# controll_8motor_dac.net
KiCad netlist of a schematic drawn in EAGLE
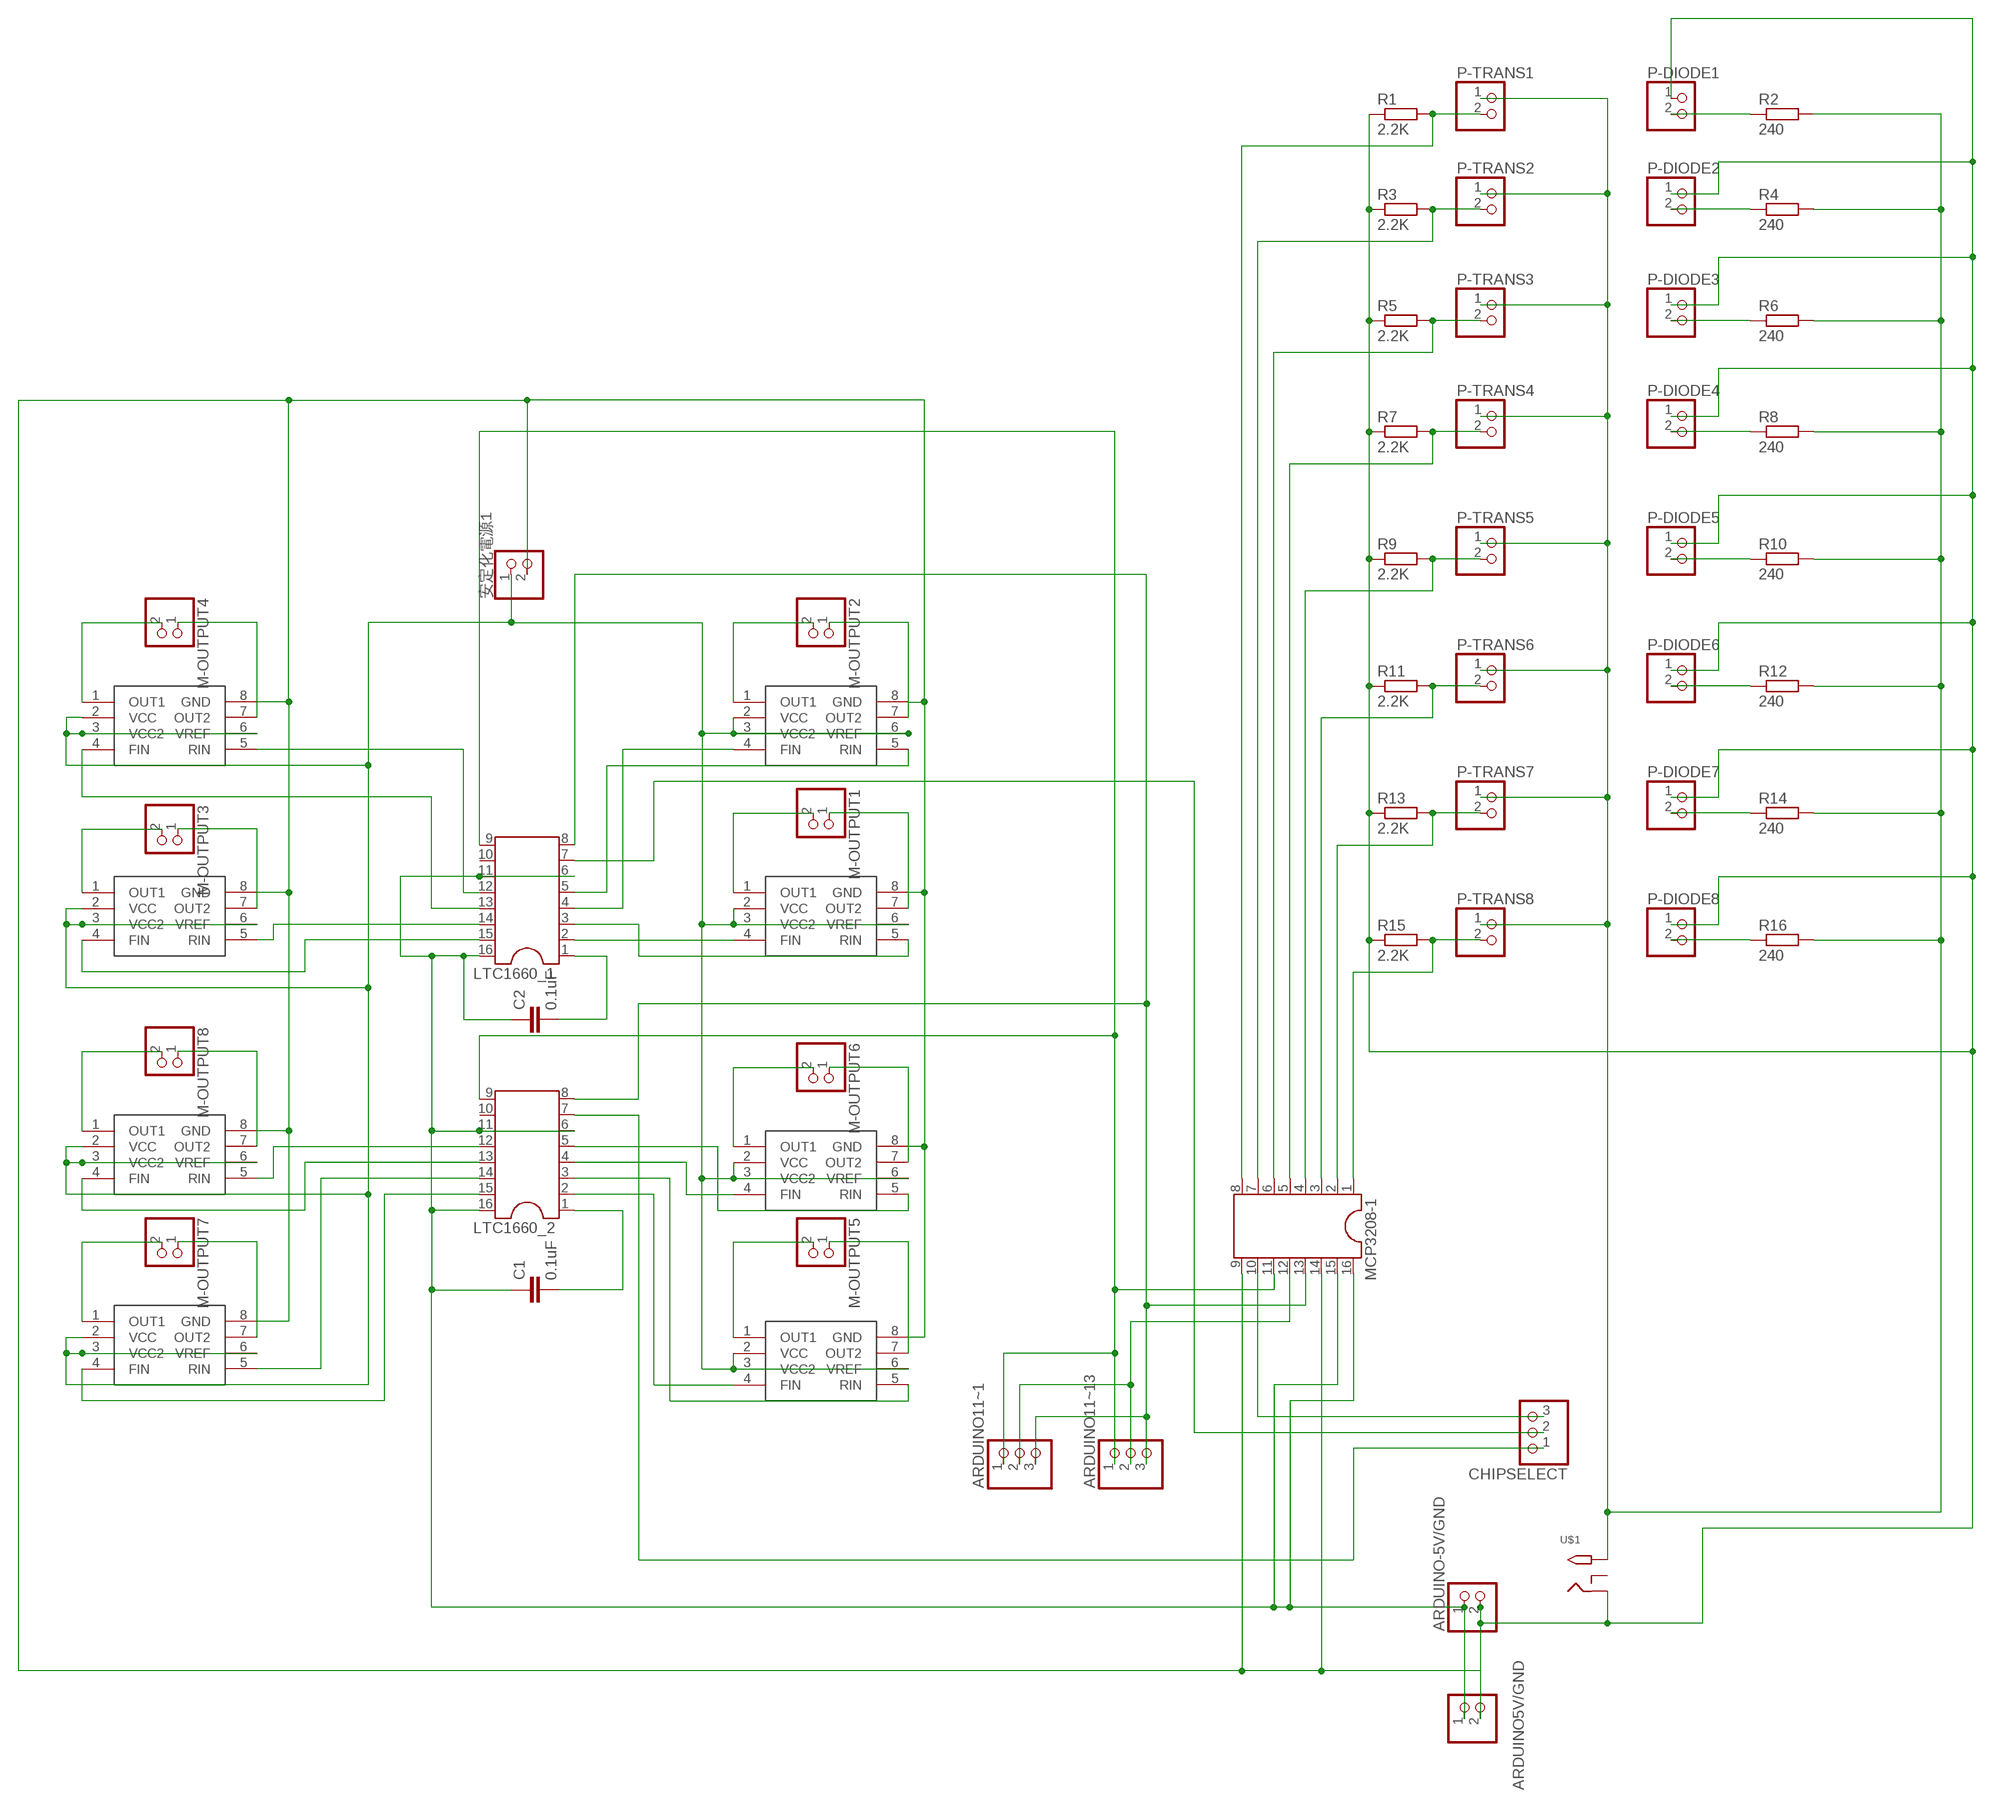
[diagram p0: schematic, sheet 1]

(export (version "E")
  (design (tool "Eeschema 10.0.6"))
  (components
    (comp (ref "ARDUINO-5V/GND")
      (value "PINHD-1X2")
      (footprint "eagle-import:1X02")
      (libsource (lib "eagle-import") (part "PINHD-1X2"))
    )
    (comp (ref "ARDUINO5V/GND")
      (value "PINHD-1X2")
      (footprint "eagle-import:1X02")
      (libsource (lib "eagle-import") (part "PINHD-1X2"))
    )
    (comp (ref "ARDUINO11~1")
      (value "PINHD-1X3")
      (footprint "eagle-import:1X03")
      (libsource (lib "eagle-import") (part "PINHD-1X3"))
    )
    (comp (ref "ARDUINO11~13")
      (value "PINHD-1X3")
      (footprint "eagle-import:1X03")
      (libsource (lib "eagle-import") (part "PINHD-1X3"))
    )
    (comp (ref "C1")
      (value "0.1uF")
      (footprint "eagle-import:C025-024X044")
      (libsource (lib "eagle-import") (part "C-EU025-024X044"))
    )
    (comp (ref "C2")
      (value "0.1uF")
      (footprint "eagle-import:C025-024X044")
      (libsource (lib "eagle-import") (part "C-EU025-024X044"))
    )
    (comp (ref "CHIPSELECT")
      (value "PINHD-1X3")
      (footprint "eagle-import:1X03")
      (libsource (lib "eagle-import") (part "PINHD-1X3"))
    )
    (comp (ref "LTC1660_1")
      (value "DIL16S")
      (footprint "eagle-import:SOCKET-16")
      (libsource (lib "eagle-import") (part "DIL16S"))
    )
    (comp (ref "LTC1660_2")
      (value "DIL16S")
      (footprint "eagle-import:SOCKET-16")
      (libsource (lib "eagle-import") (part "DIL16S"))
    )
    (comp (ref "M-DRIVER_1")
      (value "BD6211F-E2")
      (footprint "eagle-import:BD6211F-E2")
      (libsource (lib "eagle-import") (part "BD6211F-E2"))
    )
    (comp (ref "M-DRIVER_2")
      (value "BD6211F-E2")
      (footprint "eagle-import:BD6211F-E2")
      (libsource (lib "eagle-import") (part "BD6211F-E2"))
    )
    (comp (ref "M-DRIVER_3")
      (value "BD6211F-E2")
      (footprint "eagle-import:BD6211F-E2")
      (libsource (lib "eagle-import") (part "BD6211F-E2"))
    )
    (comp (ref "M-DRIVER_4")
      (value "BD6211F-E2")
      (footprint "eagle-import:BD6211F-E2")
      (libsource (lib "eagle-import") (part "BD6211F-E2"))
    )
    (comp (ref "M-DRIVER_5")
      (value "BD6211F-E2")
      (footprint "eagle-import:BD6211F-E2")
      (libsource (lib "eagle-import") (part "BD6211F-E2"))
    )
    (comp (ref "M-DRIVER_6")
      (value "BD6211F-E2")
      (footprint "eagle-import:BD6211F-E2")
      (libsource (lib "eagle-import") (part "BD6211F-E2"))
    )
    (comp (ref "M-DRIVER_7")
      (value "BD6211F-E2")
      (footprint "eagle-import:BD6211F-E2")
      (libsource (lib "eagle-import") (part "BD6211F-E2"))
    )
    (comp (ref "M-DRIVER_8")
      (value "BD6211F-E2")
      (footprint "eagle-import:BD6211F-E2")
      (libsource (lib "eagle-import") (part "BD6211F-E2"))
    )
    (comp (ref "M-OUTPUT1")
      (value "PINHD-1X2")
      (footprint "eagle-import:1X02")
      (libsource (lib "eagle-import") (part "PINHD-1X2"))
    )
    (comp (ref "M-OUTPUT2")
      (value "PINHD-1X2")
      (footprint "eagle-import:1X02")
      (libsource (lib "eagle-import") (part "PINHD-1X2"))
    )
    (comp (ref "M-OUTPUT3")
      (value "PINHD-1X2")
      (footprint "eagle-import:1X02")
      (libsource (lib "eagle-import") (part "PINHD-1X2"))
    )
    (comp (ref "M-OUTPUT4")
      (value "PINHD-1X2")
      (footprint "eagle-import:1X02")
      (libsource (lib "eagle-import") (part "PINHD-1X2"))
    )
    (comp (ref "M-OUTPUT5")
      (value "PINHD-1X2")
      (footprint "eagle-import:1X02")
      (libsource (lib "eagle-import") (part "PINHD-1X2"))
    )
    (comp (ref "M-OUTPUT6")
      (value "PINHD-1X2")
      (footprint "eagle-import:1X02")
      (libsource (lib "eagle-import") (part "PINHD-1X2"))
    )
    (comp (ref "M-OUTPUT7")
      (value "PINHD-1X2")
      (footprint "eagle-import:1X02")
      (libsource (lib "eagle-import") (part "PINHD-1X2"))
    )
    (comp (ref "M-OUTPUT8")
      (value "PINHD-1X2")
      (footprint "eagle-import:1X02")
      (libsource (lib "eagle-import") (part "PINHD-1X2"))
    )
    (comp (ref "MCP3208‐1")
      (value "DIL16S")
      (footprint "eagle-import:SOCKET-16")
      (libsource (lib "eagle-import") (part "DIL16S"))
    )
    (comp (ref "P-DIODE1")
      (value "PINHD-1X2")
      (footprint "eagle-import:1X02")
      (libsource (lib "eagle-import") (part "PINHD-1X2"))
    )
    (comp (ref "P-DIODE2")
      (value "PINHD-1X2")
      (footprint "eagle-import:1X02")
      (libsource (lib "eagle-import") (part "PINHD-1X2"))
    )
    (comp (ref "P-DIODE3")
      (value "PINHD-1X2")
      (footprint "eagle-import:1X02")
      (libsource (lib "eagle-import") (part "PINHD-1X2"))
    )
    (comp (ref "P-DIODE4")
      (value "PINHD-1X2")
      (footprint "eagle-import:1X02")
      (libsource (lib "eagle-import") (part "PINHD-1X2"))
    )
    (comp (ref "P-DIODE5")
      (value "PINHD-1X2")
      (footprint "eagle-import:1X02")
      (libsource (lib "eagle-import") (part "PINHD-1X2"))
    )
    (comp (ref "P-DIODE6")
      (value "PINHD-1X2")
      (footprint "eagle-import:1X02")
      (libsource (lib "eagle-import") (part "PINHD-1X2"))
    )
    (comp (ref "P-DIODE7")
      (value "PINHD-1X2")
      (footprint "eagle-import:1X02")
      (libsource (lib "eagle-import") (part "PINHD-1X2"))
    )
    (comp (ref "P-DIODE8")
      (value "PINHD-1X2")
      (footprint "eagle-import:1X02")
      (libsource (lib "eagle-import") (part "PINHD-1X2"))
    )
    (comp (ref "P-TRANS1")
      (value "PINHD-1X2")
      (footprint "eagle-import:1X02")
      (libsource (lib "eagle-import") (part "PINHD-1X2"))
    )
    (comp (ref "P-TRANS2")
      (value "PINHD-1X2")
      (footprint "eagle-import:1X02")
      (libsource (lib "eagle-import") (part "PINHD-1X2"))
    )
    (comp (ref "P-TRANS3")
      (value "PINHD-1X2")
      (footprint "eagle-import:1X02")
      (libsource (lib "eagle-import") (part "PINHD-1X2"))
    )
    (comp (ref "P-TRANS4")
      (value "PINHD-1X2")
      (footprint "eagle-import:1X02")
      (libsource (lib "eagle-import") (part "PINHD-1X2"))
    )
    (comp (ref "P-TRANS5")
      (value "PINHD-1X2")
      (footprint "eagle-import:1X02")
      (libsource (lib "eagle-import") (part "PINHD-1X2"))
    )
    (comp (ref "P-TRANS6")
      (value "PINHD-1X2")
      (footprint "eagle-import:1X02")
      (libsource (lib "eagle-import") (part "PINHD-1X2"))
    )
    (comp (ref "P-TRANS7")
      (value "PINHD-1X2")
      (footprint "eagle-import:1X02")
      (libsource (lib "eagle-import") (part "PINHD-1X2"))
    )
    (comp (ref "P-TRANS8")
      (value "PINHD-1X2")
      (footprint "eagle-import:1X02")
      (libsource (lib "eagle-import") (part "PINHD-1X2"))
    )
    (comp (ref "R1")
      (value "2.2K")
      (footprint "eagle-import:0204V")
      (libsource (lib "eagle-import") (part "R-EU_0204/2V"))
    )
    (comp (ref "R2")
      (value "240")
      (footprint "eagle-import:0204V")
      (libsource (lib "eagle-import") (part "R-EU_0204/2V"))
    )
    (comp (ref "R3")
      (value "2.2K")
      (footprint "eagle-import:0204V")
      (libsource (lib "eagle-import") (part "R-EU_0204/2V"))
    )
    (comp (ref "R4")
      (value "240")
      (footprint "eagle-import:0204V")
      (libsource (lib "eagle-import") (part "R-EU_0204/2V"))
    )
    (comp (ref "R5")
      (value "2.2K")
      (footprint "eagle-import:0204V")
      (libsource (lib "eagle-import") (part "R-EU_0204/2V"))
    )
    (comp (ref "R6")
      (value "240")
      (footprint "eagle-import:0204V")
      (libsource (lib "eagle-import") (part "R-EU_0204/2V"))
    )
    (comp (ref "R7")
      (value "2.2K")
      (footprint "eagle-import:0204V")
      (libsource (lib "eagle-import") (part "R-EU_0204/2V"))
    )
    (comp (ref "R8")
      (value "240")
      (footprint "eagle-import:0204V")
      (libsource (lib "eagle-import") (part "R-EU_0204/2V"))
    )
    (comp (ref "R9")
      (value "2.2K")
      (footprint "eagle-import:0204V")
      (libsource (lib "eagle-import") (part "R-EU_0204/2V"))
    )
    (comp (ref "R10")
      (value "240")
      (footprint "eagle-import:0204V")
      (libsource (lib "eagle-import") (part "R-EU_0204/2V"))
    )
    (comp (ref "R11")
      (value "2.2K")
      (footprint "eagle-import:0204V")
      (libsource (lib "eagle-import") (part "R-EU_0204/2V"))
    )
    (comp (ref "R12")
      (value "240")
      (footprint "eagle-import:0204V")
      (libsource (lib "eagle-import") (part "R-EU_0204/2V"))
    )
    (comp (ref "R13")
      (value "2.2K")
      (footprint "eagle-import:0204V")
      (libsource (lib "eagle-import") (part "R-EU_0204/2V"))
    )
    (comp (ref "R14")
      (value "240")
      (footprint "eagle-import:0204V")
      (libsource (lib "eagle-import") (part "R-EU_0204/2V"))
    )
    (comp (ref "R15")
      (value "2.2K")
      (footprint "eagle-import:0204V")
      (libsource (lib "eagle-import") (part "R-EU_0204/2V"))
    )
    (comp (ref "R16")
      (value "240")
      (footprint "eagle-import:0204V")
      (libsource (lib "eagle-import") (part "R-EU_0204/2V"))
    )
    (comp (ref "U$1")
      (value "2.1MMJACKTHM")
      (footprint "eagle-import:PJ-102A")
      (libsource (lib "eagle-import") (part "2.1MMJACKTHM"))
    )
    (comp (ref "安定化電源1")
      (value "PINHD-1X2")
      (footprint "eagle-import:1X02")
      (libsource (lib "eagle-import") (part "PINHD-1X2"))
    )
  )
  (nets
    (net (code "1") (name "Net-(ARDUINO-5V/GND-Pad1)") (class "Default")
      (node (ref "ARDUINO-5V/GND") (pin "1") (pinfunction "1_1") (pintype "passive"))
      (node (ref "ARDUINO5V/GND") (pin "1") (pinfunction "1_1") (pintype "passive"))
      (node (ref "C1") (pin "1") (pinfunction "1_1") (pintype "passive"))
      (node (ref "C2") (pin "1") (pinfunction "1_1") (pintype "passive"))
      (node (ref "LTC1660_1") (pin "11") (pinfunction "11_11") (pintype "passive"))
      (node (ref "LTC1660_1") (pin "16") (pinfunction "16_16") (pintype "passive"))
      (node (ref "LTC1660_1") (pin "6") (pinfunction "6_6") (pintype "passive"))
      (node (ref "LTC1660_2") (pin "11") (pinfunction "11_11") (pintype "passive"))
      (node (ref "LTC1660_2") (pin "16") (pinfunction "16_16") (pintype "passive"))
      (node (ref "LTC1660_2") (pin "6") (pinfunction "6_6") (pintype "passive"))
      (node (ref "MCP3208‐1") (pin "15") (pinfunction "15_15") (pintype "passive"))
      (node (ref "MCP3208‐1") (pin "16") (pinfunction "16_16") (pintype "passive"))
    )
    (net (code "2") (name "Net-(ARDUINO11~1-Pad1)") (class "Default")
      (node (ref "ARDUINO11~1") (pin "1") (pinfunction "1_1") (pintype "passive"))
      (node (ref "ARDUINO11~13") (pin "1") (pinfunction "1_1") (pintype "passive"))
      (node (ref "LTC1660_1") (pin "9") (pinfunction "9_9") (pintype "passive"))
      (node (ref "LTC1660_2") (pin "9") (pinfunction "9_9") (pintype "passive"))
      (node (ref "MCP3208‐1") (pin "11") (pinfunction "11_11") (pintype "passive"))
    )
    (net (code "3") (name "Net-(ARDUINO11~1-Pad2)") (class "Default")
      (node (ref "ARDUINO11~1") (pin "2") (pinfunction "2_2") (pintype "passive"))
      (node (ref "ARDUINO11~13") (pin "2") (pinfunction "2_2") (pintype "passive"))
      (node (ref "MCP3208‐1") (pin "12") (pinfunction "12_12") (pintype "passive"))
    )
    (net (code "4") (name "Net-(ARDUINO11~1-Pad3)") (class "Default")
      (node (ref "ARDUINO11~1") (pin "3") (pinfunction "3_3") (pintype "passive"))
      (node (ref "ARDUINO11~13") (pin "3") (pinfunction "3_3") (pintype "passive"))
      (node (ref "LTC1660_1") (pin "8") (pinfunction "8_8") (pintype "passive"))
      (node (ref "LTC1660_2") (pin "8") (pinfunction "8_8") (pintype "passive"))
      (node (ref "MCP3208‐1") (pin "13") (pinfunction "13_13") (pintype "passive"))
    )
    (net (code "5") (name "Net-(C1-Pad2)") (class "Default")
      (node (ref "C1") (pin "2") (pinfunction "2_2") (pintype "passive"))
      (node (ref "LTC1660_2") (pin "1") (pinfunction "1_1") (pintype "passive"))
    )
    (net (code "6") (name "Net-(C2-Pad2)") (class "Default")
      (node (ref "C2") (pin "2") (pinfunction "2_2") (pintype "passive"))
      (node (ref "LTC1660_1") (pin "1") (pinfunction "1_1") (pintype "passive"))
    )
    (net (code "7") (name "Net-(CHIPSELECT-Pad1)") (class "Default")
      (node (ref "CHIPSELECT") (pin "1") (pinfunction "1_1") (pintype "passive"))
      (node (ref "LTC1660_2") (pin "7") (pinfunction "7_7") (pintype "passive"))
    )
    (net (code "8") (name "Net-(CHIPSELECT-Pad2)") (class "Default")
      (node (ref "CHIPSELECT") (pin "2") (pinfunction "2_2") (pintype "passive"))
      (node (ref "LTC1660_1") (pin "7") (pinfunction "7_7") (pintype "passive"))
    )
    (net (code "9") (name "Net-(CHIPSELECT-Pad3)") (class "Default")
      (node (ref "CHIPSELECT") (pin "3") (pinfunction "3_3") (pintype "passive"))
      (node (ref "MCP3208‐1") (pin "10") (pinfunction "10_10") (pintype "passive"))
    )
    (net (code "10") (name "Net-(M-DRIVER_1-FIN)") (class "Default")
      (node (ref "LTC1660_1") (pin "2") (pinfunction "2_2") (pintype "passive"))
      (node (ref "M-DRIVER_1") (pin "4") (pinfunction "FIN_4") (pintype "bidirectional"))
    )
    (net (code "11") (name "Net-(M-DRIVER_1-GND)") (class "Default")
      (node (ref "ARDUINO-5V/GND") (pin "2") (pinfunction "2_2") (pintype "passive"))
      (node (ref "ARDUINO5V/GND") (pin "2") (pinfunction "2_2") (pintype "passive"))
      (node (ref "M-DRIVER_1") (pin "8") (pinfunction "GND_8") (pintype "bidirectional"))
      (node (ref "M-DRIVER_2") (pin "8") (pinfunction "GND_8") (pintype "bidirectional"))
      (node (ref "M-DRIVER_3") (pin "8") (pinfunction "GND_8") (pintype "bidirectional"))
      (node (ref "M-DRIVER_4") (pin "8") (pinfunction "GND_8") (pintype "bidirectional"))
      (node (ref "M-DRIVER_5") (pin "8") (pinfunction "GND_8") (pintype "bidirectional"))
      (node (ref "M-DRIVER_6") (pin "8") (pinfunction "GND_8") (pintype "bidirectional"))
      (node (ref "M-DRIVER_7") (pin "8") (pinfunction "GND_8") (pintype "bidirectional"))
      (node (ref "M-DRIVER_8") (pin "8") (pinfunction "GND_8") (pintype "bidirectional"))
      (node (ref "MCP3208‐1") (pin "14") (pinfunction "14_14") (pintype "passive"))
      (node (ref "MCP3208‐1") (pin "9") (pinfunction "9_9") (pintype "passive"))
      (node (ref "P-DIODE1") (pin "1") (pinfunction "1_1") (pintype "passive"))
      (node (ref "P-DIODE2") (pin "1") (pinfunction "1_1") (pintype "passive"))
      (node (ref "P-DIODE3") (pin "1") (pinfunction "1_1") (pintype "passive"))
      (node (ref "P-DIODE4") (pin "1") (pinfunction "1_1") (pintype "passive"))
      (node (ref "P-DIODE5") (pin "1") (pinfunction "1_1") (pintype "passive"))
      (node (ref "P-DIODE6") (pin "1") (pinfunction "1_1") (pintype "passive"))
      (node (ref "P-DIODE7") (pin "1") (pinfunction "1_1") (pintype "passive"))
      (node (ref "P-DIODE8") (pin "1") (pinfunction "1_1") (pintype "passive"))
      (node (ref "R1") (pin "1") (pinfunction "1_1") (pintype "passive"))
      (node (ref "R11") (pin "1") (pinfunction "1_1") (pintype "passive"))
      (node (ref "R13") (pin "1") (pinfunction "1_1") (pintype "passive"))
      (node (ref "R15") (pin "1") (pinfunction "1_1") (pintype "passive"))
      (node (ref "R3") (pin "1") (pinfunction "1_1") (pintype "passive"))
      (node (ref "R5") (pin "1") (pinfunction "1_1") (pintype "passive"))
      (node (ref "R7") (pin "1") (pinfunction "1_1") (pintype "passive"))
      (node (ref "R9") (pin "1") (pinfunction "1_1") (pintype "passive"))
      (node (ref "U$1") (pin "RING") (pinfunction "RING_RING") (pintype "bidirectional"))
      (node (ref "安定化電源1") (pin "2") (pinfunction "2_2") (pintype "passive"))
    )
    (net (code "12") (name "Net-(M-DRIVER_1-OUT1)") (class "Default")
      (node (ref "M-DRIVER_1") (pin "1") (pinfunction "OUT1_1") (pintype "bidirectional"))
      (node (ref "M-OUTPUT1") (pin "2") (pinfunction "2_2") (pintype "passive"))
    )
    (net (code "13") (name "Net-(M-DRIVER_1-OUT2)") (class "Default")
      (node (ref "M-DRIVER_1") (pin "7") (pinfunction "OUT2_7") (pintype "bidirectional"))
      (node (ref "M-OUTPUT1") (pin "1") (pinfunction "1_1") (pintype "passive"))
    )
    (net (code "14") (name "Net-(M-DRIVER_1-RIN)") (class "Default")
      (node (ref "LTC1660_1") (pin "3") (pinfunction "3_3") (pintype "passive"))
      (node (ref "M-DRIVER_1") (pin "5") (pinfunction "RIN_5") (pintype "bidirectional"))
    )
    (net (code "15") (name "Net-(M-DRIVER_1-VCC)") (class "Default")
      (node (ref "M-DRIVER_1") (pin "2") (pinfunction "VCC_2") (pintype "bidirectional"))
      (node (ref "M-DRIVER_1") (pin "3") (pinfunction "VCC2_3") (pintype "bidirectional"))
      (node (ref "M-DRIVER_1") (pin "6") (pinfunction "VREF_6") (pintype "bidirectional"))
      (node (ref "M-DRIVER_2") (pin "2") (pinfunction "VCC_2") (pintype "bidirectional"))
      (node (ref "M-DRIVER_2") (pin "3") (pinfunction "VCC2_3") (pintype "bidirectional"))
      (node (ref "M-DRIVER_2") (pin "6") (pinfunction "VREF_6") (pintype "bidirectional"))
      (node (ref "M-DRIVER_3") (pin "2") (pinfunction "VCC_2") (pintype "bidirectional"))
      (node (ref "M-DRIVER_3") (pin "3") (pinfunction "VCC2_3") (pintype "bidirectional"))
      (node (ref "M-DRIVER_3") (pin "6") (pinfunction "VREF_6") (pintype "bidirectional"))
      (node (ref "M-DRIVER_4") (pin "2") (pinfunction "VCC_2") (pintype "bidirectional"))
      (node (ref "M-DRIVER_4") (pin "3") (pinfunction "VCC2_3") (pintype "bidirectional"))
      (node (ref "M-DRIVER_4") (pin "6") (pinfunction "VREF_6") (pintype "bidirectional"))
      (node (ref "M-DRIVER_5") (pin "2") (pinfunction "VCC_2") (pintype "bidirectional"))
      (node (ref "M-DRIVER_5") (pin "3") (pinfunction "VCC2_3") (pintype "bidirectional"))
      (node (ref "M-DRIVER_5") (pin "6") (pinfunction "VREF_6") (pintype "bidirectional"))
      (node (ref "M-DRIVER_6") (pin "2") (pinfunction "VCC_2") (pintype "bidirectional"))
      (node (ref "M-DRIVER_6") (pin "3") (pinfunction "VCC2_3") (pintype "bidirectional"))
      (node (ref "M-DRIVER_6") (pin "6") (pinfunction "VREF_6") (pintype "bidirectional"))
      (node (ref "M-DRIVER_7") (pin "2") (pinfunction "VCC_2") (pintype "bidirectional"))
      (node (ref "M-DRIVER_7") (pin "3") (pinfunction "VCC2_3") (pintype "bidirectional"))
      (node (ref "M-DRIVER_7") (pin "6") (pinfunction "VREF_6") (pintype "bidirectional"))
      (node (ref "M-DRIVER_8") (pin "2") (pinfunction "VCC_2") (pintype "bidirectional"))
      (node (ref "M-DRIVER_8") (pin "3") (pinfunction "VCC2_3") (pintype "bidirectional"))
      (node (ref "M-DRIVER_8") (pin "6") (pinfunction "VREF_6") (pintype "bidirectional"))
      (node (ref "安定化電源1") (pin "1") (pinfunction "1_1") (pintype "passive"))
    )
    (net (code "16") (name "Net-(M-DRIVER_2-FIN)") (class "Default")
      (node (ref "LTC1660_1") (pin "4") (pinfunction "4_4") (pintype "passive"))
      (node (ref "M-DRIVER_2") (pin "4") (pinfunction "FIN_4") (pintype "bidirectional"))
    )
    (net (code "17") (name "Net-(M-DRIVER_2-OUT1)") (class "Default")
      (node (ref "M-DRIVER_2") (pin "1") (pinfunction "OUT1_1") (pintype "bidirectional"))
      (node (ref "M-OUTPUT2") (pin "2") (pinfunction "2_2") (pintype "passive"))
    )
    (net (code "18") (name "Net-(M-DRIVER_2-OUT2)") (class "Default")
      (node (ref "M-DRIVER_2") (pin "7") (pinfunction "OUT2_7") (pintype "bidirectional"))
      (node (ref "M-OUTPUT2") (pin "1") (pinfunction "1_1") (pintype "passive"))
    )
    (net (code "19") (name "Net-(M-DRIVER_2-RIN)") (class "Default")
      (node (ref "LTC1660_1") (pin "5") (pinfunction "5_5") (pintype "passive"))
      (node (ref "M-DRIVER_2") (pin "5") (pinfunction "RIN_5") (pintype "bidirectional"))
    )
    (net (code "20") (name "Net-(M-DRIVER_3-FIN)") (class "Default")
      (node (ref "LTC1660_1") (pin "15") (pinfunction "15_15") (pintype "passive"))
      (node (ref "M-DRIVER_3") (pin "4") (pinfunction "FIN_4") (pintype "bidirectional"))
    )
    (net (code "21") (name "Net-(M-DRIVER_3-OUT1)") (class "Default")
      (node (ref "M-DRIVER_3") (pin "1") (pinfunction "OUT1_1") (pintype "bidirectional"))
      (node (ref "M-OUTPUT3") (pin "2") (pinfunction "2_2") (pintype "passive"))
    )
    (net (code "22") (name "Net-(M-DRIVER_3-OUT2)") (class "Default")
      (node (ref "M-DRIVER_3") (pin "7") (pinfunction "OUT2_7") (pintype "bidirectional"))
      (node (ref "M-OUTPUT3") (pin "1") (pinfunction "1_1") (pintype "passive"))
    )
    (net (code "23") (name "Net-(M-DRIVER_3-RIN)") (class "Default")
      (node (ref "LTC1660_1") (pin "14") (pinfunction "14_14") (pintype "passive"))
      (node (ref "M-DRIVER_3") (pin "5") (pinfunction "RIN_5") (pintype "bidirectional"))
    )
    (net (code "24") (name "Net-(M-DRIVER_4-FIN)") (class "Default")
      (node (ref "LTC1660_1") (pin "13") (pinfunction "13_13") (pintype "passive"))
      (node (ref "M-DRIVER_4") (pin "4") (pinfunction "FIN_4") (pintype "bidirectional"))
    )
    (net (code "25") (name "Net-(M-DRIVER_4-OUT1)") (class "Default")
      (node (ref "M-DRIVER_4") (pin "1") (pinfunction "OUT1_1") (pintype "bidirectional"))
      (node (ref "M-OUTPUT4") (pin "2") (pinfunction "2_2") (pintype "passive"))
    )
    (net (code "26") (name "Net-(M-DRIVER_4-OUT2)") (class "Default")
      (node (ref "M-DRIVER_4") (pin "7") (pinfunction "OUT2_7") (pintype "bidirectional"))
      (node (ref "M-OUTPUT4") (pin "1") (pinfunction "1_1") (pintype "passive"))
    )
    (net (code "27") (name "Net-(M-DRIVER_4-RIN)") (class "Default")
      (node (ref "LTC1660_1") (pin "12") (pinfunction "12_12") (pintype "passive"))
      (node (ref "M-DRIVER_4") (pin "5") (pinfunction "RIN_5") (pintype "bidirectional"))
    )
    (net (code "28") (name "Net-(M-DRIVER_5-FIN)") (class "Default")
      (node (ref "LTC1660_2") (pin "2") (pinfunction "2_2") (pintype "passive"))
      (node (ref "M-DRIVER_5") (pin "4") (pinfunction "FIN_4") (pintype "bidirectional"))
    )
    (net (code "29") (name "Net-(M-DRIVER_5-OUT1)") (class "Default")
      (node (ref "M-DRIVER_5") (pin "1") (pinfunction "OUT1_1") (pintype "bidirectional"))
      (node (ref "M-OUTPUT5") (pin "2") (pinfunction "2_2") (pintype "passive"))
    )
    (net (code "30") (name "Net-(M-DRIVER_5-OUT2)") (class "Default")
      (node (ref "M-DRIVER_5") (pin "7") (pinfunction "OUT2_7") (pintype "bidirectional"))
      (node (ref "M-OUTPUT5") (pin "1") (pinfunction "1_1") (pintype "passive"))
    )
    (net (code "31") (name "Net-(M-DRIVER_5-RIN)") (class "Default")
      (node (ref "LTC1660_2") (pin "3") (pinfunction "3_3") (pintype "passive"))
      (node (ref "M-DRIVER_5") (pin "5") (pinfunction "RIN_5") (pintype "bidirectional"))
    )
    (net (code "32") (name "Net-(M-DRIVER_6-FIN)") (class "Default")
      (node (ref "LTC1660_2") (pin "4") (pinfunction "4_4") (pintype "passive"))
      (node (ref "M-DRIVER_6") (pin "4") (pinfunction "FIN_4") (pintype "bidirectional"))
    )
    (net (code "33") (name "Net-(M-DRIVER_6-OUT1)") (class "Default")
      (node (ref "M-DRIVER_6") (pin "1") (pinfunction "OUT1_1") (pintype "bidirectional"))
      (node (ref "M-OUTPUT6") (pin "2") (pinfunction "2_2") (pintype "passive"))
    )
    (net (code "34") (name "Net-(M-DRIVER_6-OUT2)") (class "Default")
      (node (ref "M-DRIVER_6") (pin "7") (pinfunction "OUT2_7") (pintype "bidirectional"))
      (node (ref "M-OUTPUT6") (pin "1") (pinfunction "1_1") (pintype "passive"))
    )
    (net (code "35") (name "Net-(M-DRIVER_6-RIN)") (class "Default")
      (node (ref "LTC1660_2") (pin "5") (pinfunction "5_5") (pintype "passive"))
      (node (ref "M-DRIVER_6") (pin "5") (pinfunction "RIN_5") (pintype "bidirectional"))
    )
    (net (code "36") (name "Net-(M-DRIVER_7-FIN)") (class "Default")
      (node (ref "LTC1660_2") (pin "15") (pinfunction "15_15") (pintype "passive"))
      (node (ref "M-DRIVER_7") (pin "4") (pinfunction "FIN_4") (pintype "bidirectional"))
    )
    (net (code "37") (name "Net-(M-DRIVER_7-OUT1)") (class "Default")
      (node (ref "M-DRIVER_7") (pin "1") (pinfunction "OUT1_1") (pintype "bidirectional"))
      (node (ref "M-OUTPUT7") (pin "2") (pinfunction "2_2") (pintype "passive"))
    )
    (net (code "38") (name "Net-(M-DRIVER_7-OUT2)") (class "Default")
      (node (ref "M-DRIVER_7") (pin "7") (pinfunction "OUT2_7") (pintype "bidirectional"))
      (node (ref "M-OUTPUT7") (pin "1") (pinfunction "1_1") (pintype "passive"))
    )
    (net (code "39") (name "Net-(M-DRIVER_7-RIN)") (class "Default")
      (node (ref "LTC1660_2") (pin "14") (pinfunction "14_14") (pintype "passive"))
      (node (ref "M-DRIVER_7") (pin "5") (pinfunction "RIN_5") (pintype "bidirectional"))
    )
    (net (code "40") (name "Net-(M-DRIVER_8-FIN)") (class "Default")
      (node (ref "LTC1660_2") (pin "13") (pinfunction "13_13") (pintype "passive"))
      (node (ref "M-DRIVER_8") (pin "4") (pinfunction "FIN_4") (pintype "bidirectional"))
    )
    (net (code "41") (name "Net-(M-DRIVER_8-OUT1)") (class "Default")
      (node (ref "M-DRIVER_8") (pin "1") (pinfunction "OUT1_1") (pintype "bidirectional"))
      (node (ref "M-OUTPUT8") (pin "2") (pinfunction "2_2") (pintype "passive"))
    )
    (net (code "42") (name "Net-(M-DRIVER_8-OUT2)") (class "Default")
      (node (ref "M-DRIVER_8") (pin "7") (pinfunction "OUT2_7") (pintype "bidirectional"))
      (node (ref "M-OUTPUT8") (pin "1") (pinfunction "1_1") (pintype "passive"))
    )
    (net (code "43") (name "Net-(M-DRIVER_8-RIN)") (class "Default")
      (node (ref "LTC1660_2") (pin "12") (pinfunction "12_12") (pintype "passive"))
      (node (ref "M-DRIVER_8") (pin "5") (pinfunction "RIN_5") (pintype "bidirectional"))
    )
    (net (code "44") (name "Net-(MCP3208‐1-Pad1)") (class "Default")
      (node (ref "MCP3208‐1") (pin "1") (pinfunction "1_1") (pintype "passive"))
      (node (ref "P-TRANS8") (pin "2") (pinfunction "2_2") (pintype "passive"))
      (node (ref "R15") (pin "2") (pinfunction "2_2") (pintype "passive"))
    )
    (net (code "45") (name "Net-(MCP3208‐1-Pad2)") (class "Default")
      (node (ref "MCP3208‐1") (pin "2") (pinfunction "2_2") (pintype "passive"))
      (node (ref "P-TRANS7") (pin "2") (pinfunction "2_2") (pintype "passive"))
      (node (ref "R13") (pin "2") (pinfunction "2_2") (pintype "passive"))
    )
    (net (code "46") (name "Net-(MCP3208‐1-Pad3)") (class "Default")
      (node (ref "MCP3208‐1") (pin "3") (pinfunction "3_3") (pintype "passive"))
      (node (ref "P-TRANS6") (pin "2") (pinfunction "2_2") (pintype "passive"))
      (node (ref "R11") (pin "2") (pinfunction "2_2") (pintype "passive"))
    )
    (net (code "47") (name "Net-(MCP3208‐1-Pad4)") (class "Default")
      (node (ref "MCP3208‐1") (pin "4") (pinfunction "4_4") (pintype "passive"))
      (node (ref "P-TRANS5") (pin "2") (pinfunction "2_2") (pintype "passive"))
      (node (ref "R9") (pin "2") (pinfunction "2_2") (pintype "passive"))
    )
    (net (code "48") (name "Net-(MCP3208‐1-Pad5)") (class "Default")
      (node (ref "MCP3208‐1") (pin "5") (pinfunction "5_5") (pintype "passive"))
      (node (ref "P-TRANS4") (pin "2") (pinfunction "2_2") (pintype "passive"))
      (node (ref "R7") (pin "2") (pinfunction "2_2") (pintype "passive"))
    )
    (net (code "49") (name "Net-(MCP3208‐1-Pad6)") (class "Default")
      (node (ref "MCP3208‐1") (pin "6") (pinfunction "6_6") (pintype "passive"))
      (node (ref "P-TRANS3") (pin "2") (pinfunction "2_2") (pintype "passive"))
      (node (ref "R5") (pin "2") (pinfunction "2_2") (pintype "passive"))
    )
    (net (code "50") (name "Net-(MCP3208‐1-Pad7)") (class "Default")
      (node (ref "MCP3208‐1") (pin "7") (pinfunction "7_7") (pintype "passive"))
      (node (ref "P-TRANS2") (pin "2") (pinfunction "2_2") (pintype "passive"))
      (node (ref "R3") (pin "2") (pinfunction "2_2") (pintype "passive"))
    )
    (net (code "51") (name "Net-(MCP3208‐1-Pad8)") (class "Default")
      (node (ref "MCP3208‐1") (pin "8") (pinfunction "8_8") (pintype "passive"))
      (node (ref "P-TRANS1") (pin "2") (pinfunction "2_2") (pintype "passive"))
      (node (ref "R1") (pin "2") (pinfunction "2_2") (pintype "passive"))
    )
    (net (code "52") (name "Net-(P-DIODE1-Pad2)") (class "Default")
      (node (ref "P-DIODE1") (pin "2") (pinfunction "2_2") (pintype "passive"))
      (node (ref "R2") (pin "1") (pinfunction "1_1") (pintype "passive"))
    )
    (net (code "53") (name "Net-(P-DIODE2-Pad2)") (class "Default")
      (node (ref "P-DIODE2") (pin "2") (pinfunction "2_2") (pintype "passive"))
      (node (ref "R4") (pin "1") (pinfunction "1_1") (pintype "passive"))
    )
    (net (code "54") (name "Net-(P-DIODE3-Pad2)") (class "Default")
      (node (ref "P-DIODE3") (pin "2") (pinfunction "2_2") (pintype "passive"))
      (node (ref "R6") (pin "1") (pinfunction "1_1") (pintype "passive"))
    )
    (net (code "55") (name "Net-(P-DIODE4-Pad2)") (class "Default")
      (node (ref "P-DIODE4") (pin "2") (pinfunction "2_2") (pintype "passive"))
      (node (ref "R8") (pin "1") (pinfunction "1_1") (pintype "passive"))
    )
    (net (code "56") (name "Net-(P-DIODE5-Pad2)") (class "Default")
      (node (ref "P-DIODE5") (pin "2") (pinfunction "2_2") (pintype "passive"))
      (node (ref "R10") (pin "1") (pinfunction "1_1") (pintype "passive"))
    )
    (net (code "57") (name "Net-(P-DIODE6-Pad2)") (class "Default")
      (node (ref "P-DIODE6") (pin "2") (pinfunction "2_2") (pintype "passive"))
      (node (ref "R12") (pin "1") (pinfunction "1_1") (pintype "passive"))
    )
    (net (code "58") (name "Net-(P-DIODE7-Pad2)") (class "Default")
      (node (ref "P-DIODE7") (pin "2") (pinfunction "2_2") (pintype "passive"))
      (node (ref "R14") (pin "1") (pinfunction "1_1") (pintype "passive"))
    )
    (net (code "59") (name "Net-(P-DIODE8-Pad2)") (class "Default")
      (node (ref "P-DIODE8") (pin "2") (pinfunction "2_2") (pintype "passive"))
      (node (ref "R16") (pin "1") (pinfunction "1_1") (pintype "passive"))
    )
    (net (code "60") (name "Net-(P-TRANS1-Pad1)") (class "Default")
      (node (ref "P-TRANS1") (pin "1") (pinfunction "1_1") (pintype "passive"))
      (node (ref "P-TRANS2") (pin "1") (pinfunction "1_1") (pintype "passive"))
      (node (ref "P-TRANS3") (pin "1") (pinfunction "1_1") (pintype "passive"))
      (node (ref "P-TRANS4") (pin "1") (pinfunction "1_1") (pintype "passive"))
      (node (ref "P-TRANS5") (pin "1") (pinfunction "1_1") (pintype "passive"))
      (node (ref "P-TRANS6") (pin "1") (pinfunction "1_1") (pintype "passive"))
      (node (ref "P-TRANS7") (pin "1") (pinfunction "1_1") (pintype "passive"))
      (node (ref "P-TRANS8") (pin "1") (pinfunction "1_1") (pintype "passive"))
      (node (ref "R10") (pin "2") (pinfunction "2_2") (pintype "passive"))
      (node (ref "R12") (pin "2") (pinfunction "2_2") (pintype "passive"))
      (node (ref "R14") (pin "2") (pinfunction "2_2") (pintype "passive"))
      (node (ref "R16") (pin "2") (pinfunction "2_2") (pintype "passive"))
      (node (ref "R2") (pin "2") (pinfunction "2_2") (pintype "passive"))
      (node (ref "R4") (pin "2") (pinfunction "2_2") (pintype "passive"))
      (node (ref "R6") (pin "2") (pinfunction "2_2") (pintype "passive"))
      (node (ref "R8") (pin "2") (pinfunction "2_2") (pintype "passive"))
      (node (ref "U$1") (pin "TIP") (pinfunction "TIP_TIP") (pintype "bidirectional"))
    )
    (net (code "61") (name "unconnected-(LTC1660_1-Pad10)") (class "Default")
      (node (ref "LTC1660_1") (pin "10") (pinfunction "10_10") (pintype "passive"))
    )
    (net (code "62") (name "unconnected-(LTC1660_2-Pad10)") (class "Default")
      (node (ref "LTC1660_2") (pin "10") (pinfunction "10_10") (pintype "passive"))
    )
    (net (code "63") (name "unconnected-(U$1-PadRING_SW)") (class "Default")
      (node (ref "U$1") (pin "RING_SW") (pinfunction "RING_SW_RING_SW") (pintype "bidirectional"))
    )
  )
)
